# wifinfo_esp01.net
KiCad netlist of a schematic drawn in EAGLE
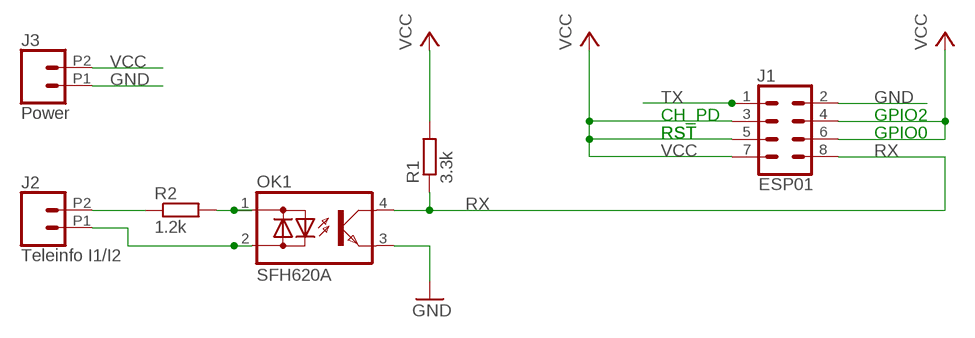
[diagram p0: schematic, sheet 1]

(export (version "E")
  (design (tool "Eeschema 10.0.6"))
  (components
    (comp (ref "J1")
      (value "ESP01")
      (footprint "eagle-import:2X4")
      (libsource (lib "eagle-import") (part "CONN_04X2"))
    )
    (comp (ref "J2")
      (value "Teleinfo I1/I2")
      (footprint "eagle-import:1X02_2.54_SCREWTERM")
      (libsource (lib "eagle-import") (part "CONN_022.54MM_SCREWTERM"))
    )
    (comp (ref "J3")
      (value "Power")
      (footprint "eagle-import:1X02_2.54_SCREWTERM")
      (libsource (lib "eagle-import") (part "CONN_022.54MM_SCREWTERM"))
    )
    (comp (ref "OK1")
      (value "SFH620A")
      (footprint "eagle-import:DIL04")
      (fields (field (name "MPN") "SFH620A-2"))
      (libsource (lib "eagle-import") (part "SFH620A"))
    )
    (comp (ref "R1")
      (value "3.3k")
      (footprint "eagle-import:0204_7")
      (libsource (lib "eagle-import") (part "R-EU_0204/7"))
    )
    (comp (ref "R2")
      (value "1.2k")
      (footprint "eagle-import:0204_7")
      (libsource (lib "eagle-import") (part "R-EU_0204/7"))
    )
  )
  (nets
    (net (code "1") (name "/RX") (class "Default")
      (node (ref "J1") (pin "8") (pinfunction "8_8") (pintype "passive"))
      (node (ref "OK1") (pin "4") (pinfunction "C_4") (pintype "passive"))
      (node (ref "R1") (pin "1") (pinfunction "1_1") (pintype "passive"))
    )
    (net (code "2") (name "/TX") (class "Default")
      (node (ref "J1") (pin "1") (pinfunction "1_1") (pintype "passive"))
    )
    (net (code "3") (name "GND") (class "Default")
      (node (ref "J1") (pin "2") (pinfunction "2_2") (pintype "passive"))
      (node (ref "J3") (pin "P1") (pinfunction "1_P1") (pintype "passive"))
      (node (ref "OK1") (pin "3") (pinfunction "E_3") (pintype "passive"))
    )
    (net (code "4") (name "Net-(J2-1)") (class "Default")
      (node (ref "J2") (pin "P1") (pinfunction "1_P1") (pintype "passive"))
      (node (ref "OK1") (pin "2") (pinfunction "AC2_2") (pintype "passive"))
    )
    (net (code "5") (name "Net-(J2-2)") (class "Default")
      (node (ref "J2") (pin "P2") (pinfunction "2_P2") (pintype "passive"))
      (node (ref "R2") (pin "1") (pinfunction "1_1") (pintype "passive"))
    )
    (net (code "6") (name "Net-(OK1-AC1)") (class "Default")
      (node (ref "OK1") (pin "1") (pinfunction "AC1_1") (pintype "passive"))
      (node (ref "R2") (pin "2") (pinfunction "2_2") (pintype "passive"))
    )
    (net (code "7") (name "VCC") (class "Default")
      (node (ref "J1") (pin "3") (pinfunction "3_3") (pintype "passive"))
      (node (ref "J1") (pin "4") (pinfunction "4_4") (pintype "passive"))
      (node (ref "J1") (pin "5") (pinfunction "5_5") (pintype "passive"))
      (node (ref "J1") (pin "6") (pinfunction "6_6") (pintype "passive"))
      (node (ref "J1") (pin "7") (pinfunction "7_7") (pintype "passive"))
      (node (ref "J3") (pin "P2") (pinfunction "2_P2") (pintype "passive"))
      (node (ref "R1") (pin "2") (pinfunction "2_2") (pintype "passive"))
    )
  )
)
